# FMC_SFP_ADAPTER_SFP.net
KiCad netlist of a schematic drawn in Altium Designer
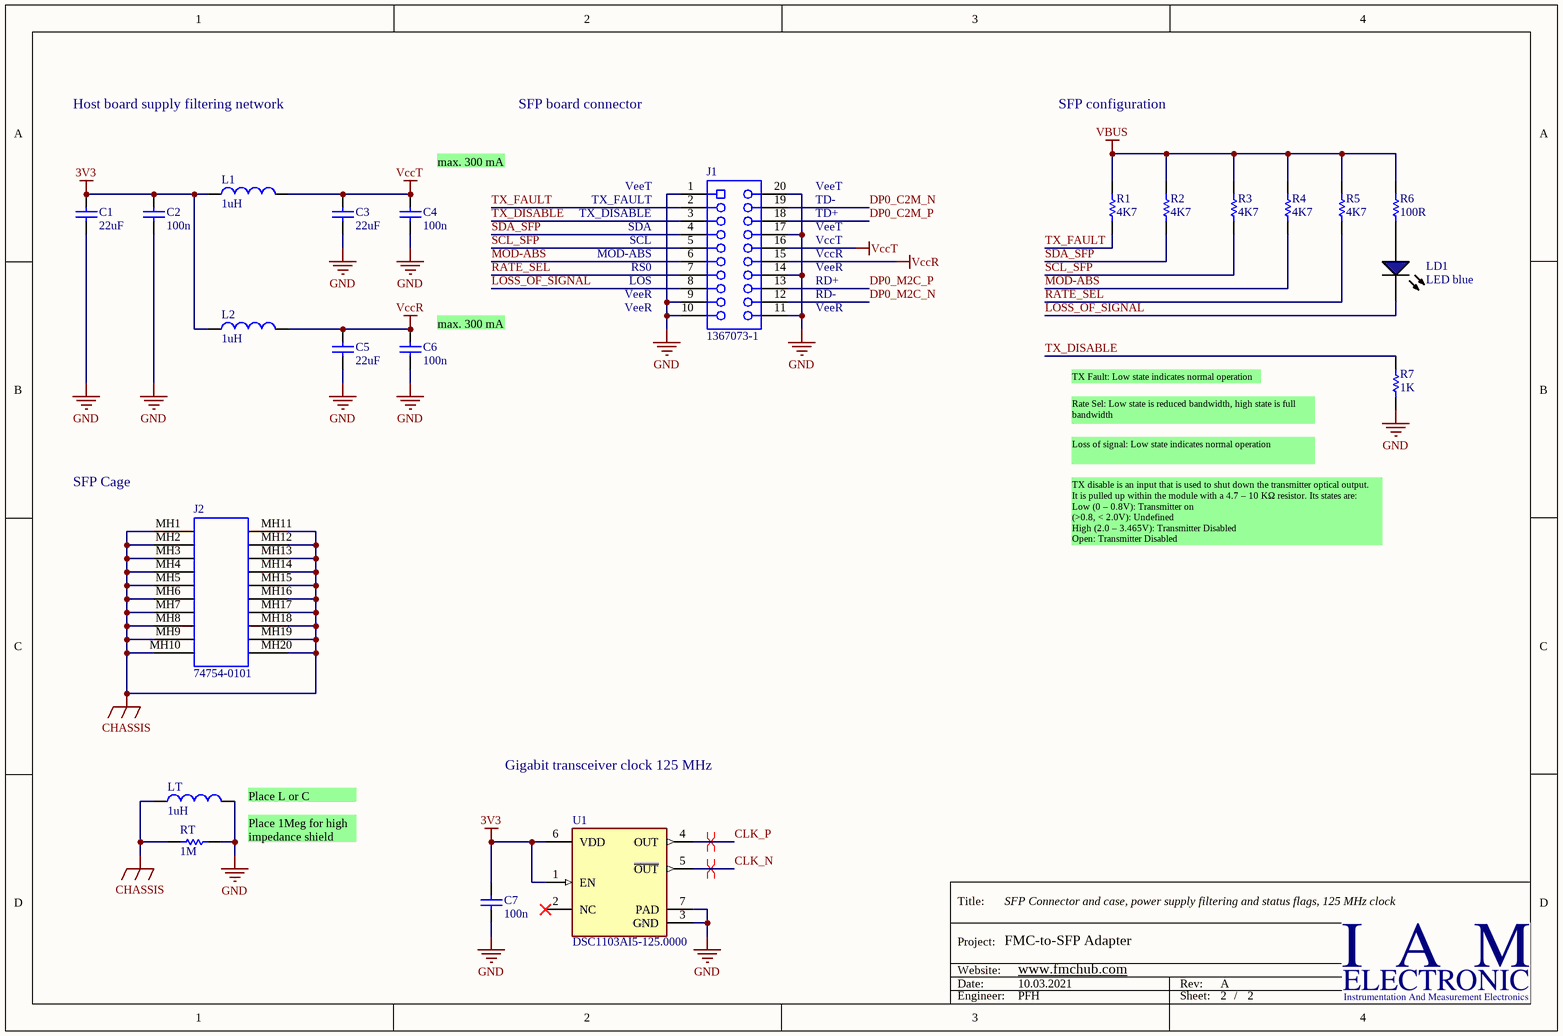
[diagram p0: FMC_SFP_ADAPTER_SFP.SchDoc]

(export (version "E")
  (design (tool "Eeschema 10.0.6"))
  (components
    (comp (ref "C1")
      (value "22uF")
      (footprint "CAPC1206(3216)190_L")
      (description "CAP 22uF 6.3V X5R ±10% 1206 (3216 Metric) Thickness 1.9mm SMD")
      (fields (field (name "TOLERANCE") "±10%") (field (name "PART") "JMK316ABJ226KL-T"))
      (libsource (lib "Altium Content Vault") (part "CMP-1037-04985-1"))
    )
    (comp (ref "C2")
      (value "100n")
      (footprint "CAPC1005X55X25ML05T10")
      (description "Chip Capacitor, 0.1 uF, +/- 10%, 16 V, -55 to 125 degC, 0402 (1005 Metric), RoHS, Tape and Reel")
      (fields (field (name "VOLTAGE") "16V") (field (name "TOLERANCE") "10%"))
      (libsource (lib "Altium Content Vault") (part "CAP-NP-2"))
    )
    (comp (ref "C3")
      (value "22uF")
      (footprint "CAPC1206(3216)190_L")
      (description "CAP 22uF 6.3V X5R ±10% 1206 (3216 Metric) Thickness 1.9mm SMD")
      (fields (field (name "TOLERANCE") "±10%") (field (name "PART") "JMK316ABJ226KL-T"))
      (libsource (lib "Altium Content Vault") (part "CMP-1037-04985-1"))
    )
    (comp (ref "C4")
      (value "100n")
      (footprint "CAPC1005X55X25ML05T10")
      (description "Chip Capacitor, 0.1 uF, +/- 10%, 16 V, -55 to 125 degC, 0402 (1005 Metric), RoHS, Tape and Reel")
      (fields (field (name "VOLTAGE") "16V") (field (name "TOLERANCE") "10%"))
      (libsource (lib "Altium Content Vault") (part "CAP-NP-2"))
    )
    (comp (ref "C5")
      (value "22uF")
      (footprint "CAPC1206(3216)190_L")
      (description "CAP 22uF 6.3V X5R ±10% 1206 (3216 Metric) Thickness 1.9mm SMD")
      (fields (field (name "TOLERANCE") "±10%") (field (name "PART") "JMK316ABJ226KL-T"))
      (libsource (lib "Altium Content Vault") (part "CMP-1037-04985-1"))
    )
    (comp (ref "C6")
      (value "100n")
      (footprint "CAPC1005X55X25ML05T10")
      (description "Chip Capacitor, 0.1 uF, +/- 10%, 16 V, -55 to 125 degC, 0402 (1005 Metric), RoHS, Tape and Reel")
      (fields (field (name "VOLTAGE") "16V") (field (name "TOLERANCE") "10%"))
      (libsource (lib "Altium Content Vault") (part "CAP-NP-2"))
    )
    (comp (ref "C7")
      (value "100n")
      (footprint "CAPC1005X55X25ML05T10")
      (description "Chip Capacitor, 0.1 uF, +/- 10%, 16 V, -55 to 125 degC, 0402 (1005 Metric), RoHS, Tape and Reel")
      (fields (field (name "VOLTAGE") "16V") (field (name "TOLERANCE") "10%"))
      (libsource (lib "Altium Content Vault") (part "CAP-NP-2"))
    )
    (comp (ref "J1")
      (value "1367073-1")
      (footprint "TECO-1367073-1_V")
      (fields (field (name "MANUFACTURER") "TE Connectivity"))
      (libsource (lib "Altium Content Vault") (part "CN-2P-F-R20_B"))
    )
    (comp (ref "J2")
      (value "74754-0101")
      (footprint "MOLX-74754-0101_V")
      (description "SFP+ Cage, Single Port, Height 10.85 mm, Tail Height 3.05 mm, -40 to 85 degC, RoHS, Tray")
      (fields (field (name "MANUFACTURER") "Molex"))
      (libsource (lib "Altium Content Vault") (part "MOLX-74754-0101"))
    )
    (comp (ref "L1")
      (value "1uH")
      (footprint "MURA-IND0805_H_0.55_L")
      (description "Chip Inductor, 1.0 uH, +/- 20%, -55 to 125 degC, 2-Pin SMD (0805), RoHS, Tape and Reel")
      (fields (field (name "MANUFACTURER") "Murata") (field (name "PART") "LQM21PN1R0MC0D"))
      (libsource (lib "Altium Content Vault") (part "IND-2"))
    )
    (comp (ref "L2")
      (value "1uH")
      (footprint "MURA-IND0805_H_0.55_L")
      (description "Chip Inductor, 1.0 uH, +/- 20%, -55 to 125 degC, 2-Pin SMD (0805), RoHS, Tape and Reel")
      (fields (field (name "MANUFACTURER") "Murata") (field (name "PART") "LQM21PN1R0MC0D"))
      (libsource (lib "Altium Content Vault") (part "IND-2"))
    )
    (comp (ref "LD1")
      (value "LED blue")
      (footprint "LED0603")
      (description "LED blue, SMD 0603")
      (fields (field (name "PART") "LTST-C190TBKT") (field (name "MANUFACTURER") "Lite-On"))
      (libsource (lib "LEDs") (part "LED_BLUE"))
    )
    (comp (ref "LT")
      (value "1uH")
      (footprint "MURA-IND0805_H_0.55_L")
      (description "Chip Inductor, 1.0 uH, +/- 20%, -55 to 125 degC, 2-Pin SMD (0805), RoHS, Tape and Reel")
      (fields (field (name "MANUFACTURER") "Murata") (field (name "PART") "LQM21PN1R0MC0D"))
      (libsource (lib "Altium Content Vault") (part "IND-2"))
    )
    (comp (ref "R1")
      (value "4K7")
      (footprint "RESC1005X40X25ML05T05")
      (description "Chip Resistor, 4.7 KOhm, +/- 1%, 63 mW, -55 to 155 degC, 0402 (1005 Metric), RoHS, Tape and Reel")
      (fields (field (name "PARTNUMBER") "CRCW04024K70FKED") (field (name "TOLERANCE") "1%"))
      (libsource (lib "Altium Content Vault") (part "RES"))
    )
    (comp (ref "R2")
      (value "4K7")
      (footprint "RESC1005X40X25ML05T05")
      (description "Chip Resistor, 4.7 KOhm, +/- 1%, 63 mW, -55 to 155 degC, 0402 (1005 Metric), RoHS, Tape and Reel")
      (fields (field (name "PARTNUMBER") "CRCW04024K70FKED") (field (name "TOLERANCE") "1%"))
      (libsource (lib "Altium Content Vault") (part "RES"))
    )
    (comp (ref "R3")
      (value "4K7")
      (footprint "RESC1005X40X25ML05T05")
      (description "Chip Resistor, 4.7 KOhm, +/- 1%, 63 mW, -55 to 155 degC, 0402 (1005 Metric), RoHS, Tape and Reel")
      (fields (field (name "PARTNUMBER") "CRCW04024K70FKED") (field (name "TOLERANCE") "1%"))
      (libsource (lib "Altium Content Vault") (part "RES"))
    )
    (comp (ref "R4")
      (value "4K7")
      (footprint "RESC1005X40X25ML05T05")
      (description "Chip Resistor, 4.7 KOhm, +/- 1%, 63 mW, -55 to 155 degC, 0402 (1005 Metric), RoHS, Tape and Reel")
      (fields (field (name "PARTNUMBER") "CRCW04024K70FKED") (field (name "TOLERANCE") "1%"))
      (libsource (lib "Altium Content Vault") (part "RES"))
    )
    (comp (ref "R5")
      (value "4K7")
      (footprint "RESC1005X40X25ML05T05")
      (description "Chip Resistor, 4.7 KOhm, +/- 1%, 63 mW, -55 to 155 degC, 0402 (1005 Metric), RoHS, Tape and Reel")
      (fields (field (name "PARTNUMBER") "CRCW04024K70FKED") (field (name "TOLERANCE") "1%"))
      (libsource (lib "Altium Content Vault") (part "RES"))
    )
    (comp (ref "R6")
      (value "100R")
      (footprint "RESC0603(1608)_N")
      (description "100R 0.1W 1% 0603 (1608 Metric)  SMD")
      (fields (field (name "TOLERANCE") "1 %") (field (name "POWER") "0.1 W"))
      (libsource (lib "Altium Content Vault") (part "CMP-1012-00397-1"))
    )
    (comp (ref "R7")
      (value "1K")
      (footprint "RESC1608X55X25NL10T15")
      (description "Chip Resistor, 1 KOhm, +/-1%, 0.1 W, -55 to 155 degC, 0603 (1608 Metric), RoHS, Tape and Reel")
      (fields (field (name "MANUFACTURER") "Yageo") (field (name "PART") "RC0603FR-071KL"))
      (libsource (lib "Altium Content Vault") (part "RES-2"))
    )
    (comp (ref "RT")
      (value "1M")
      (footprint "RESC0805(2012)_L")
      (fields
        (field (name "TOLERANCE") "5 %")
        (field (name "POWER") "0.125 W")
        (field (name "PART") "RC0805JR-071ML")
      )
      (libsource (lib "Altium Content Vault") (part "CMP-1013-00146-1"))
    )
    (comp (ref "U1")
      (value "DSC1103AI5-125.0000")
      (footprint "FP-C04-1010-MFG")
      (description "MEMS OSC XO 125.0000MHZ LVDS SMD")
      (fields
        (field (name "MANUFACTURER") "Microchip")
        (field (name "OCTOPART") "https://octopart.com/dsc1103al1-100.0000-microchip-87209273")
      )
      (libsource (lib "Altium Content Vault") (part "5156a08486e60b4e5d3eb43614889a8"))
    )
  )
  (nets
    (net (code "1") (name "/CLK_N") (class "Default")
      (node (ref "U1") (pin "5") (pinfunction "~{OUT}_5") (pintype "output"))
    )
    (net (code "2") (name "/CLK_P") (class "Default")
      (node (ref "U1") (pin "4") (pinfunction "OUT_4") (pintype "output"))
    )
    (net (code "3") (name "/DP0_C2M_N") (class "Default")
      (node (ref "J1") (pin "19") (pinfunction "19_19") (pintype "passive"))
    )
    (net (code "4") (name "/DP0_C2M_P") (class "Default")
      (node (ref "J1") (pin "18") (pinfunction "18_18") (pintype "passive"))
    )
    (net (code "5") (name "/DP0_M2C_N") (class "Default")
      (node (ref "J1") (pin "12") (pinfunction "12_12") (pintype "passive"))
    )
    (net (code "6") (name "/DP0_M2C_P") (class "Default")
      (node (ref "J1") (pin "13") (pinfunction "13_13") (pintype "passive"))
    )
    (net (code "7") (name "/LOSS_OF_SIGNAL") (class "Default")
      (node (ref "J1") (pin "8") (pinfunction "8_8") (pintype "passive"))
      (node (ref "LD1") (pin "2") (pinfunction "K_2") (pintype "passive"))
    )
    (net (code "8") (name "/MOD-ABS") (class "Default")
      (node (ref "J1") (pin "6") (pinfunction "6_6") (pintype "passive"))
      (node (ref "R4") (pin "1") (pinfunction "1_1") (pintype "passive"))
    )
    (net (code "9") (name "/RATE_SEL") (class "Default")
      (node (ref "J1") (pin "7") (pinfunction "7_7") (pintype "passive"))
      (node (ref "R5") (pin "1") (pinfunction "1_1") (pintype "passive"))
    )
    (net (code "10") (name "/SCL_SFP") (class "Default")
      (node (ref "J1") (pin "5") (pinfunction "5_5") (pintype "passive"))
      (node (ref "R3") (pin "1") (pinfunction "1_1") (pintype "passive"))
    )
    (net (code "11") (name "/SDA_SFP") (class "Default")
      (node (ref "J1") (pin "4") (pinfunction "4_4") (pintype "passive"))
      (node (ref "R2") (pin "1") (pinfunction "1_1") (pintype "passive"))
    )
    (net (code "12") (name "/TX_DISABLE") (class "Default")
      (node (ref "J1") (pin "3") (pinfunction "3_3") (pintype "passive"))
      (node (ref "R7") (pin "2") (pinfunction "2_2") (pintype "passive"))
    )
    (net (code "13") (name "/TX_FAULT") (class "Default")
      (node (ref "J1") (pin "2") (pinfunction "2_2") (pintype "passive"))
      (node (ref "R1") (pin "1") (pinfunction "1_1") (pintype "passive"))
    )
    (net (code "14") (name "3V3") (class "Default")
      (node (ref "C1") (pin "2") (pinfunction "2_2") (pintype "passive"))
      (node (ref "C2") (pin "2") (pinfunction "2_2") (pintype "passive"))
      (node (ref "C7") (pin "1") (pinfunction "1_1") (pintype "passive"))
      (node (ref "L1") (pin "1") (pinfunction "1_1") (pintype "passive"))
      (node (ref "L2") (pin "1") (pinfunction "1_1") (pintype "passive"))
      (node (ref "U1") (pin "1") (pinfunction "EN_1") (pintype "input"))
      (node (ref "U1") (pin "6") (pinfunction "VDD_6") (pintype "power_in"))
    )
    (net (code "15") (name "CHASSIS") (class "Default")
      (node (ref "J2") (pin "MH1") (pinfunction "MH1_MH1") (pintype "passive"))
      (node (ref "J2") (pin "MH10") (pinfunction "MH10_MH10") (pintype "passive"))
      (node (ref "J2") (pin "MH11") (pinfunction "MH11_MH11") (pintype "passive"))
      (node (ref "J2") (pin "MH12") (pinfunction "MH12_MH12") (pintype "passive"))
      (node (ref "J2") (pin "MH13") (pinfunction "MH13_MH13") (pintype "passive"))
      (node (ref "J2") (pin "MH14") (pinfunction "MH14_MH14") (pintype "passive"))
      (node (ref "J2") (pin "MH15") (pinfunction "MH15_MH15") (pintype "passive"))
      (node (ref "J2") (pin "MH16") (pinfunction "MH16_MH16") (pintype "passive"))
      (node (ref "J2") (pin "MH17") (pinfunction "MH17_MH17") (pintype "passive"))
      (node (ref "J2") (pin "MH18") (pinfunction "MH18_MH18") (pintype "passive"))
      (node (ref "J2") (pin "MH19") (pinfunction "MH19_MH19") (pintype "passive"))
      (node (ref "J2") (pin "MH2") (pinfunction "MH2_MH2") (pintype "passive"))
      (node (ref "J2") (pin "MH20") (pinfunction "MH20_MH20") (pintype "passive"))
      (node (ref "J2") (pin "MH3") (pinfunction "MH3_MH3") (pintype "passive"))
      (node (ref "J2") (pin "MH4") (pinfunction "MH4_MH4") (pintype "passive"))
      (node (ref "J2") (pin "MH5") (pinfunction "MH5_MH5") (pintype "passive"))
      (node (ref "J2") (pin "MH6") (pinfunction "MH6_MH6") (pintype "passive"))
      (node (ref "J2") (pin "MH7") (pinfunction "MH7_MH7") (pintype "passive"))
      (node (ref "J2") (pin "MH8") (pinfunction "MH8_MH8") (pintype "passive"))
      (node (ref "J2") (pin "MH9") (pinfunction "MH9_MH9") (pintype "passive"))
      (node (ref "LT") (pin "1") (pinfunction "1_1") (pintype "passive"))
      (node (ref "RT") (pin "2") (pinfunction "2_2") (pintype "passive"))
    )
    (net (code "16") (name "GND") (class "Default")
      (node (ref "C1") (pin "1") (pinfunction "1_1") (pintype "passive"))
      (node (ref "C2") (pin "1") (pinfunction "1_1") (pintype "passive"))
      (node (ref "C3") (pin "1") (pinfunction "1_1") (pintype "passive"))
      (node (ref "C4") (pin "1") (pinfunction "1_1") (pintype "passive"))
      (node (ref "C5") (pin "1") (pinfunction "1_1") (pintype "passive"))
      (node (ref "C6") (pin "1") (pinfunction "1_1") (pintype "passive"))
      (node (ref "C7") (pin "2") (pinfunction "2_2") (pintype "passive"))
      (node (ref "J1") (pin "1") (pinfunction "1_1") (pintype "passive"))
      (node (ref "J1") (pin "10") (pinfunction "10_10") (pintype "passive"))
      (node (ref "J1") (pin "11") (pinfunction "11_11") (pintype "passive"))
      (node (ref "J1") (pin "14") (pinfunction "14_14") (pintype "passive"))
      (node (ref "J1") (pin "17") (pinfunction "17_17") (pintype "passive"))
      (node (ref "J1") (pin "20") (pinfunction "20_20") (pintype "passive"))
      (node (ref "J1") (pin "9") (pinfunction "9_9") (pintype "passive"))
      (node (ref "LT") (pin "2") (pinfunction "2_2") (pintype "passive"))
      (node (ref "R7") (pin "1") (pinfunction "1_1") (pintype "passive"))
      (node (ref "RT") (pin "1") (pinfunction "1_1") (pintype "passive"))
      (node (ref "U1") (pin "3") (pinfunction "GND_3") (pintype "power_in"))
      (node (ref "U1") (pin "7") (pinfunction "PAD_7") (pintype "power_in"))
    )
    (net (code "17") (name "Net-(LD1-A)") (class "Default")
      (node (ref "LD1") (pin "1") (pinfunction "A_1") (pintype "passive"))
      (node (ref "R6") (pin "1") (pinfunction "1_1") (pintype "passive"))
    )
    (net (code "18") (name "VBUS") (class "Default")
      (node (ref "R1") (pin "2") (pinfunction "2_2") (pintype "passive"))
      (node (ref "R2") (pin "2") (pinfunction "2_2") (pintype "passive"))
      (node (ref "R3") (pin "2") (pinfunction "2_2") (pintype "passive"))
      (node (ref "R4") (pin "2") (pinfunction "2_2") (pintype "passive"))
      (node (ref "R5") (pin "2") (pinfunction "2_2") (pintype "passive"))
      (node (ref "R6") (pin "2") (pinfunction "2_2") (pintype "passive"))
    )
    (net (code "19") (name "VccR") (class "Default")
      (node (ref "C5") (pin "2") (pinfunction "2_2") (pintype "passive"))
      (node (ref "C6") (pin "2") (pinfunction "2_2") (pintype "passive"))
      (node (ref "J1") (pin "15") (pinfunction "15_15") (pintype "passive"))
      (node (ref "L2") (pin "2") (pinfunction "2_2") (pintype "passive"))
    )
    (net (code "20") (name "VccT") (class "Default")
      (node (ref "C3") (pin "2") (pinfunction "2_2") (pintype "passive"))
      (node (ref "C4") (pin "2") (pinfunction "2_2") (pintype "passive"))
      (node (ref "J1") (pin "16") (pinfunction "16_16") (pintype "passive"))
      (node (ref "L1") (pin "2") (pinfunction "2_2") (pintype "passive"))
    )
    (net (code "21") (name "unconnected-(U1-NC-Pad2)") (class "Default")
      (node (ref "U1") (pin "2") (pinfunction "NC_2") (pintype "passive+no_connect"))
    )
  )
)
